# DetectorOptode.net
KiCad netlist of a schematic drawn in Altium Designer
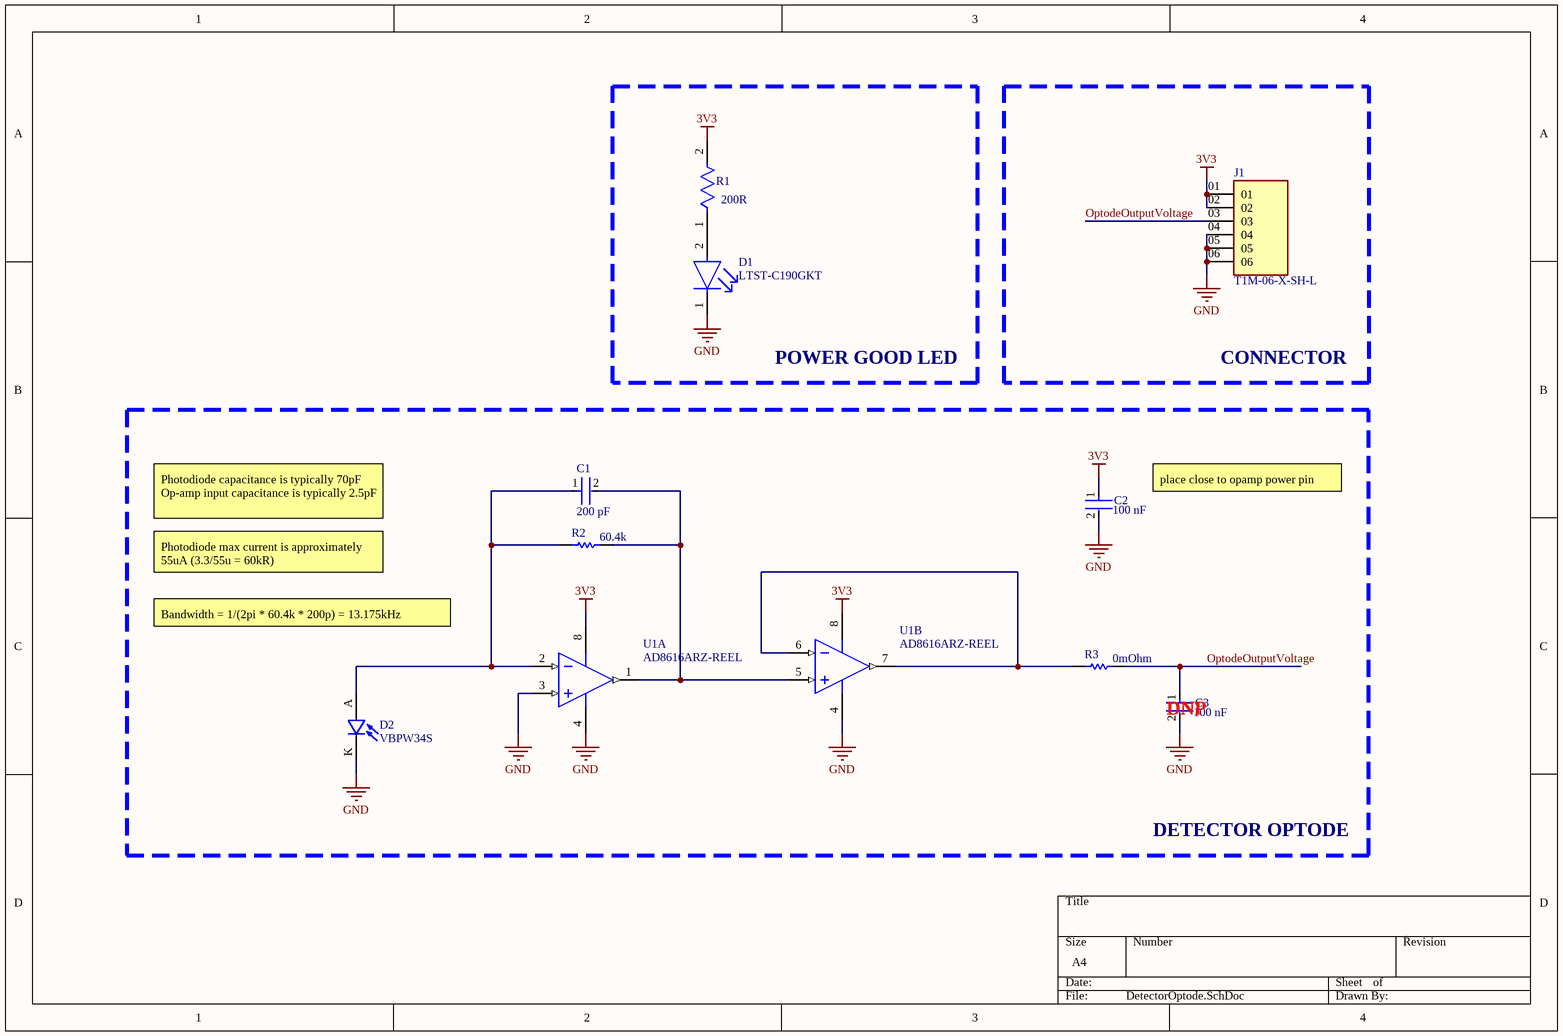
[diagram p0: DetectorOptode.SchDoc]

(export (version "E")
  (design (tool "Eeschema 10.0.6"))
  (components
    (comp (ref "C1")
      (value "C0603C201J5GACTU")
      (footprint "FP-C0603C-CF-MFG")
      (description "CAP CER 200PF 50V 5% NP0 0603")
      (fields
        (field (name "CAPACITANCE") "200 pF")
        (field (name "MANUFACTURER") "KEMET")
        (field (name "OCTOPART") "https://octopart.com/c0603c201j5gactu-kemet-9143917")
      )
      (libsource (lib "Altium Content Vault") (part "b4654b650e69147ec39a6b967a45e02"))
    )
    (comp (ref "C2")
      (value "CC0603KRX7R7BB104")
      (footprint "FP-CC0603-DA-MFG")
      (description "CAP CER 0.1UF 16V X7R 0603")
      (fields
        (field (name "OCTOPART") "https://octopart.com/cc0603krx7r7bb104-yageo-192941")
        (field (name "TOLERANCE") "0.1")
        (field (name "CAPACITANCE") "100 nF")
      )
      (libsource (lib "Altium Content Vault") (part "11868f565c42a9108669ba33697ecf6"))
    )
    (comp (ref "C3")
      (value "CC0603KRX7R7BB104")
      (footprint "FP-CC0603-DA-MFG")
      (description "CAP CER 0.1UF 16V X7R 0603")
      (fields
        (field (name "OCTOPART") "https://octopart.com/cc0603krx7r7bb104-yageo-192941")
        (field (name "TOLERANCE") "0.1")
        (field (name "CAPACITANCE") "100 nF")
      )
      (libsource (lib "Altium Content Vault") (part "11868f565c42a9108669ba33697ecf6"))
    )
    (comp (ref "D1")
      (value "LTST-C190GKT")
      (footprint "FP-LTST-C190GKT-MFG")
      (description "LED GREEN CLEAR CHIP SMD")
      (fields (field (name "VOLTAGE") "2V"))
      (libsource (lib "Altium Content Vault") (part "8706943c75ba83719d021d2fdc84c58"))
    )
    (comp (ref "D2")
      (value "VBPW34S")
      (footprint "PcbLib1:XDCR_VBPW34S")
      (description "Photodiode 940nm 100ns 130Â° 2-SMD, Gull Wing")
      (fields (field (name "MF") "Vishay"))
      (libsource (lib "SourceOptode") (part "VBPW34S"))
    )
    (comp (ref "J1")
      (value "T1M-06-X-SH-L")
      (footprint "SAMTEC_T1M-06-X-SH-L")
      (description "Connector Header Surface Mount, Right Angle 6 position 0.039\" (1.00mm)")
      (fields (field (name "MF") "Samtec"))
      (libsource (lib "SourceOptode") (part "T1M-06-X-SH-L"))
    )
    (comp (ref "R1")
      (value "CRCW0603200RFKEA")
      (footprint "FP-CRCW0603-e3-MFG")
      (description "RES Thick Film, 200Ω, 1%, 0.1W, 100ppm/°C, 0603")
      (fields (field (name "TOLERANCE") "1%") (field (name "RESISTANCE") "200R"))
      (libsource (lib "Altium Content Vault") (part "1029c3af85768c4190bb7ad29bc67b5"))
    )
    (comp (ref "R2")
      (value "RC0603FR-0760K4L")
      (footprint "RESC1608X55X25ML10T15")
      (fields (field (name "MANUFACTURER") "Yageo") (field (name "RESISTANCE") "60.4k"))
      (libsource (lib "Altium Content Vault") (part "RES"))
    )
    (comp (ref "R3")
      (value "RC0603JR-070RL")
      (footprint "RESC1608X55X25ML10T15")
      (description "Chip Resistor, 0 Ohm, +/- 5%, 0.1 W, -55 to 155 degC, 0603 (1608 Metric), RoHS, Tape and Reel")
      (fields
        (field (name "TOLERANCE") "5%")
        (field (name "RESISTANCE") "0mOhm")
        (field (name "MANUFACTURER") "Yageo")
      )
      (libsource (lib "Altium Content Vault") (part "RES-2"))
    )
    (comp (ref "U1")
      (value "AD8616ARZ-REEL")
      (footprint "ADI-R-8_N")
      (fields (field (name "MANUFACTURER") "Analog Devices") (field (name "GENERIC PART NUMBER") "AD8616"))
      (libsource (lib "Altium Content Vault") (part "ADI-OP29X-R-8"))
    )
  )
  (nets
    (net (code "1") (name "/OptodeOutputVoltage") (class "Default")
      (node (ref "C3") (pin "1") (pinfunction "1_1") (pintype "passive"))
      (node (ref "J1") (pin "03") (pinfunction "03_03") (pintype "passive"))
      (node (ref "R3") (pin "2") (pinfunction "2_2") (pintype "passive"))
    )
    (net (code "2") (name "3V3") (class "Default")
      (node (ref "C2") (pin "1") (pinfunction "1_1") (pintype "passive"))
      (node (ref "J1") (pin "01") (pinfunction "01_01") (pintype "passive"))
      (node (ref "J1") (pin "02") (pinfunction "02_02") (pintype "passive"))
      (node (ref "R1") (pin "2") (pinfunction "2_2") (pintype "passive"))
      (node (ref "U1") (pin "8") (pinfunction "+V_8") (pintype "power_in"))
    )
    (net (code "3") (name "GND") (class "Default")
      (node (ref "C2") (pin "2") (pinfunction "2_2") (pintype "passive"))
      (node (ref "C3") (pin "2") (pinfunction "2_2") (pintype "passive"))
      (node (ref "D1") (pin "1") (pinfunction "C_1") (pintype "passive"))
      (node (ref "D2") (pin "K") (pinfunction "C_K") (pintype "passive"))
      (node (ref "J1") (pin "04") (pinfunction "04_04") (pintype "passive"))
      (node (ref "J1") (pin "05") (pinfunction "05_05") (pintype "passive"))
      (node (ref "J1") (pin "06") (pinfunction "06_06") (pintype "passive"))
      (node (ref "U1") (pin "3") (pinfunction "+IN_A_3") (pintype "input"))
      (node (ref "U1") (pin "4") (pinfunction "-V_4") (pintype "power_in"))
    )
    (net (code "4") (name "Net-(D1-A)") (class "Default")
      (node (ref "D1") (pin "2") (pinfunction "A_2") (pintype "passive"))
      (node (ref "R1") (pin "1") (pinfunction "1_1") (pintype "passive"))
    )
    (net (code "5") (name "Net-(U1A--IN_A)") (class "Default")
      (node (ref "C1") (pin "1") (pinfunction "1_1") (pintype "passive"))
      (node (ref "D2") (pin "A") (pinfunction "A_A") (pintype "passive"))
      (node (ref "R2") (pin "1") (pinfunction "1_1") (pintype "passive"))
      (node (ref "U1") (pin "2") (pinfunction "-IN_A_2") (pintype "input"))
    )
    (net (code "6") (name "Net-(U1A-OUT_A)") (class "Default")
      (node (ref "C1") (pin "2") (pinfunction "2_2") (pintype "passive"))
      (node (ref "R2") (pin "2") (pinfunction "2_2") (pintype "passive"))
      (node (ref "U1") (pin "1") (pinfunction "OUT_A_1") (pintype "output"))
      (node (ref "U1") (pin "5") (pinfunction "+IN_B_5") (pintype "input"))
    )
    (net (code "7") (name "Net-(U1B--IN_B)") (class "Default")
      (node (ref "R3") (pin "1") (pinfunction "1_1") (pintype "passive"))
      (node (ref "U1") (pin "6") (pinfunction "-IN_B_6") (pintype "input"))
      (node (ref "U1") (pin "7") (pinfunction "OUT_B_7") (pintype "output"))
    )
  )
)
